# Gambar_Teknik_Danu_Kartiko_K.net
KiCad netlist of a schematic drawn in EAGLE
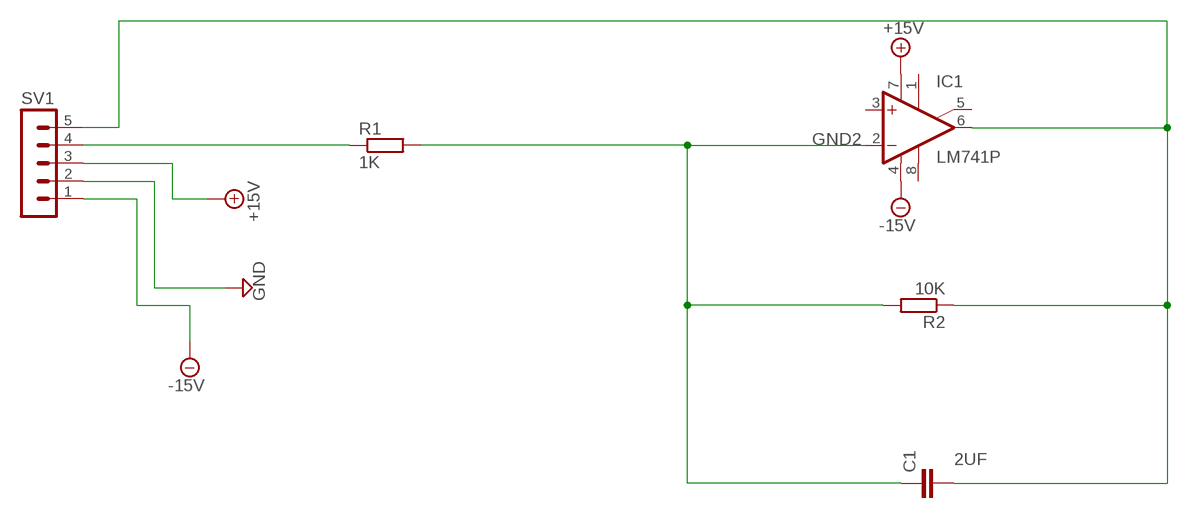
[diagram p0: schematic, sheet 1]

(export (version "E")
  (design (tool "Eeschema 10.0.6"))
  (components
    (comp (ref "C1")
      (value "C-EU025-024X044")
      (footprint "eagle-import:C025-024X044")
      (libsource (lib "eagle-import") (part "C-EU025-024X044"))
    )
    (comp (ref "IC1")
      (value "LM741P")
      (footprint "eagle-import:DIL08")
      (libsource (lib "eagle-import") (part "741PLM"))
    )
    (comp (ref "R1")
      (value "1K")
      (footprint "eagle-import:0204V")
      (libsource (lib "eagle-import") (part "R-EU_0204/2V"))
    )
    (comp (ref "R2")
      (value "10K")
      (footprint "eagle-import:0204V")
      (libsource (lib "eagle-import") (part "R-EU_0204/2V"))
    )
    (comp (ref "SV1")
      (value "MA05-1")
      (footprint "eagle-import:MA05-1")
      (libsource (lib "eagle-import") (part "MA05-1"))
    )
  )
  (nets
    (net (code "1") (name "+15V") (class "Default")
      (node (ref "IC1") (pin "7") (pinfunction "V+_7") (pintype "power_in"))
      (node (ref "SV1") (pin "3") (pinfunction "3_3") (pintype "passive"))
    )
    (net (code "2") (name "-15V") (class "Default")
      (node (ref "IC1") (pin "4") (pinfunction "V-_4") (pintype "power_in"))
      (node (ref "SV1") (pin "1") (pinfunction "1_1") (pintype "passive"))
    )
    (net (code "3") (name "/2UF") (class "Default")
      (node (ref "C1") (pin "2") (pinfunction "2_2") (pintype "passive"))
      (node (ref "IC1") (pin "6") (pinfunction "OUT_6") (pintype "output"))
      (node (ref "R2") (pin "1") (pinfunction "1_1") (pintype "passive"))
      (node (ref "SV1") (pin "5") (pinfunction "5_5") (pintype "passive"))
    )
    (net (code "4") (name "/GND2") (class "Default")
      (node (ref "C1") (pin "1") (pinfunction "1_1") (pintype "passive"))
      (node (ref "IC1") (pin "2") (pinfunction "-IN_2") (pintype "input"))
      (node (ref "R1") (pin "2") (pinfunction "2_2") (pintype "passive"))
      (node (ref "R2") (pin "2") (pinfunction "2_2") (pintype "passive"))
    )
    (net (code "5") (name "GND") (class "Default")
      (node (ref "SV1") (pin "2") (pinfunction "2_2") (pintype "passive"))
    )
    (net (code "6") (name "Net-(R1-Pad1)") (class "Default")
      (node (ref "R1") (pin "1") (pinfunction "1_1") (pintype "passive"))
      (node (ref "SV1") (pin "4") (pinfunction "4_4") (pintype "passive"))
    )
    (net (code "7") (name "unconnected-(IC1-+IN-Pad3)") (class "Default")
      (node (ref "IC1") (pin "3") (pinfunction "+IN_3") (pintype "input"))
    )
    (net (code "8") (name "unconnected-(IC1-ON1-Pad1)") (class "Default")
      (node (ref "IC1") (pin "1") (pinfunction "ON1_1") (pintype "passive"))
    )
    (net (code "9") (name "unconnected-(IC1-ON2-Pad5)") (class "Default")
      (node (ref "IC1") (pin "5") (pinfunction "ON2_5") (pintype "passive"))
    )
    (net (code "10") (name "unconnected-(IC1-OPT-Pad8)") (class "Default")
      (node (ref "IC1") (pin "8") (pinfunction "OPT_8") (pintype "passive"))
    )
  )
)
